# B137X.net
KiCad netlist of a schematic drawn in EAGLE
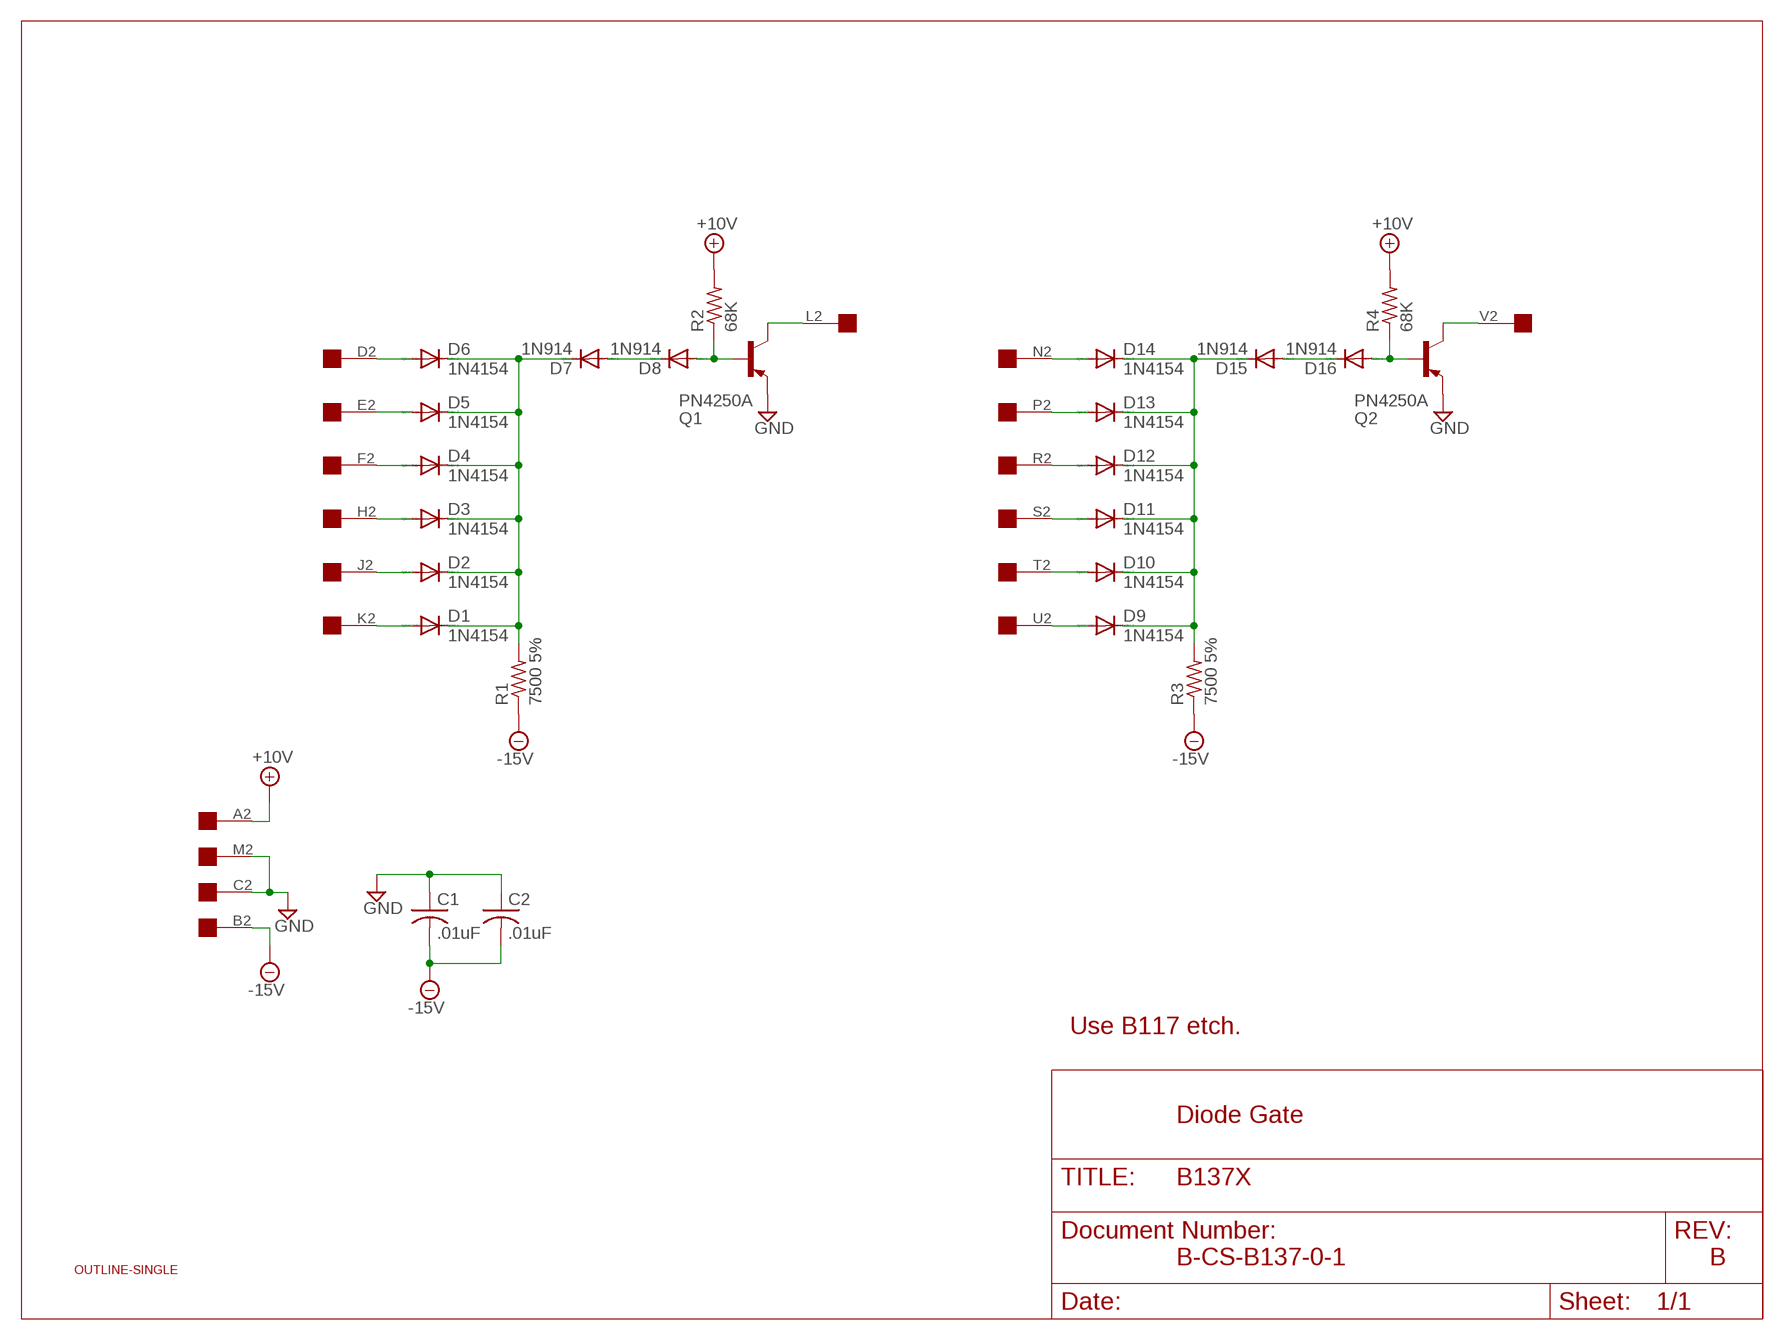
[diagram p0: schematic, sheet 1]

(export (version "E")
  (design (tool "Eeschema 10.0.6"))
  (components
    (comp (ref "C1")
      (value ".01uF")
      (footprint "eagle-import:C050-025X075")
      (libsource (lib "eagle-import") (part "C-US050-025X075"))
    )
    (comp (ref "C2")
      (value ".01uF")
      (footprint "eagle-import:C050-025X075")
      (libsource (lib "eagle-import") (part "C-US050-025X075"))
    )
    (comp (ref "D1")
      (value "1N4154")
      (footprint "eagle-import:DO35-10")
      (libsource (lib "eagle-import") (part "DIODE-DO35-10"))
    )
    (comp (ref "D2")
      (value "1N4154")
      (footprint "eagle-import:DO35-10")
      (libsource (lib "eagle-import") (part "DIODE-DO35-10"))
    )
    (comp (ref "D3")
      (value "1N4154")
      (footprint "eagle-import:DO35-10")
      (libsource (lib "eagle-import") (part "DIODE-DO35-10"))
    )
    (comp (ref "D4")
      (value "1N4154")
      (footprint "eagle-import:DO35-10")
      (libsource (lib "eagle-import") (part "DIODE-DO35-10"))
    )
    (comp (ref "D5")
      (value "1N4154")
      (footprint "eagle-import:DO35-10")
      (libsource (lib "eagle-import") (part "DIODE-DO35-10"))
    )
    (comp (ref "D6")
      (value "1N4154")
      (footprint "eagle-import:DO35-10")
      (libsource (lib "eagle-import") (part "DIODE-DO35-10"))
    )
    (comp (ref "D7")
      (value "1N914")
      (footprint "eagle-import:DO35-10")
      (libsource (lib "eagle-import") (part "DIODE-DO35-10"))
    )
    (comp (ref "D8")
      (value "1N914")
      (footprint "eagle-import:DO35-10")
      (libsource (lib "eagle-import") (part "DIODE-DO35-10"))
    )
    (comp (ref "D9")
      (value "1N4154")
      (footprint "eagle-import:DO35-10")
      (libsource (lib "eagle-import") (part "DIODE-DO35-10"))
    )
    (comp (ref "D10")
      (value "1N4154")
      (footprint "eagle-import:DO35-10")
      (libsource (lib "eagle-import") (part "DIODE-DO35-10"))
    )
    (comp (ref "D11")
      (value "1N4154")
      (footprint "eagle-import:DO35-10")
      (libsource (lib "eagle-import") (part "DIODE-DO35-10"))
    )
    (comp (ref "D12")
      (value "1N4154")
      (footprint "eagle-import:DO35-10")
      (libsource (lib "eagle-import") (part "DIODE-DO35-10"))
    )
    (comp (ref "D13")
      (value "1N4154")
      (footprint "eagle-import:DO35-10")
      (libsource (lib "eagle-import") (part "DIODE-DO35-10"))
    )
    (comp (ref "D14")
      (value "1N4154")
      (footprint "eagle-import:DO35-10")
      (libsource (lib "eagle-import") (part "DIODE-DO35-10"))
    )
    (comp (ref "D15")
      (value "1N914")
      (footprint "eagle-import:DO35-10")
      (libsource (lib "eagle-import") (part "DIODE-DO35-10"))
    )
    (comp (ref "D16")
      (value "1N914")
      (footprint "eagle-import:DO35-10")
      (libsource (lib "eagle-import") (part "DIODE-DO35-10"))
    )
    (comp (ref "Q1")
      (value "PN4250A")
      (footprint "eagle-import:TO5")
      (libsource (lib "eagle-import") (part "-PNP-TO5"))
    )
    (comp (ref "Q2")
      (value "PN4250A")
      (footprint "eagle-import:TO5")
      (libsource (lib "eagle-import") (part "-PNP-TO5"))
    )
    (comp (ref "R1")
      (value "7500 5%")
      (footprint "eagle-import:0207_10")
      (libsource (lib "eagle-import") (part "R-US_0207/10"))
    )
    (comp (ref "R2")
      (value "68K")
      (footprint "eagle-import:0207_10")
      (libsource (lib "eagle-import") (part "R-US_0207/10"))
    )
    (comp (ref "R3")
      (value "7500 5%")
      (footprint "eagle-import:0207_10")
      (libsource (lib "eagle-import") (part "R-US_0207/10"))
    )
    (comp (ref "R4")
      (value "68K")
      (footprint "eagle-import:0207_10")
      (libsource (lib "eagle-import") (part "R-US_0207/10"))
    )
    (comp (ref "U$1")
      (value "OUTLINE-SINGLE")
      (footprint "eagle-import:SINGLE")
      (libsource (lib "eagle-import") (part "OUTLINE-SINGLE"))
    )
    (comp (ref "U$2")
      (value "EDGE-1")
      (footprint "eagle-import:EDGE-CON1")
      (libsource (lib "eagle-import") (part "EDGE-1"))
    )
  )
  (nets
    (net (code "1") (name "+10V") (class "Default")
      (node (ref "R2") (pin "2") (pinfunction "2_2") (pintype "passive"))
      (node (ref "R4") (pin "2") (pinfunction "2_2") (pintype "passive"))
      (node (ref "U$2") (pin "A2") (pinfunction "1_A2") (pintype "bidirectional"))
    )
    (net (code "2") (name "-15V") (class "Default")
      (node (ref "C1") (pin "2") (pinfunction "2_2") (pintype "passive"))
      (node (ref "C2") (pin "2") (pinfunction "2_2") (pintype "passive"))
      (node (ref "R1") (pin "1") (pinfunction "1_1") (pintype "passive"))
      (node (ref "R3") (pin "1") (pinfunction "1_1") (pintype "passive"))
      (node (ref "U$2") (pin "B2") (pinfunction "1_B2") (pintype "bidirectional"))
    )
    (net (code "3") (name "GND") (class "Default")
      (node (ref "C1") (pin "1") (pinfunction "1_1") (pintype "passive"))
      (node (ref "C2") (pin "1") (pinfunction "1_1") (pintype "passive"))
      (node (ref "Q1") (pin "1") (pinfunction "E_1") (pintype "passive"))
      (node (ref "Q2") (pin "1") (pinfunction "E_1") (pintype "passive"))
      (node (ref "U$2") (pin "C2") (pinfunction "1_C2") (pintype "bidirectional"))
      (node (ref "U$2") (pin "M2") (pinfunction "1_M2") (pintype "bidirectional"))
    )
    (net (code "4") (name "Net-(D1-PadC)") (class "Default")
      (node (ref "D1") (pin "C") (pinfunction "C_C") (pintype "passive"))
      (node (ref "D2") (pin "C") (pinfunction "C_C") (pintype "passive"))
      (node (ref "D3") (pin "C") (pinfunction "C_C") (pintype "passive"))
      (node (ref "D4") (pin "C") (pinfunction "C_C") (pintype "passive"))
      (node (ref "D5") (pin "C") (pinfunction "C_C") (pintype "passive"))
      (node (ref "D6") (pin "C") (pinfunction "C_C") (pintype "passive"))
      (node (ref "D7") (pin "C") (pinfunction "C_C") (pintype "passive"))
      (node (ref "R1") (pin "2") (pinfunction "2_2") (pintype "passive"))
    )
    (net (code "5") (name "Net-(D7-PadA)") (class "Default")
      (node (ref "D7") (pin "A") (pinfunction "A_A") (pintype "passive"))
      (node (ref "D8") (pin "C") (pinfunction "C_C") (pintype "passive"))
    )
    (net (code "6") (name "Net-(D10-PadC)") (class "Default")
      (node (ref "D10") (pin "C") (pinfunction "C_C") (pintype "passive"))
      (node (ref "D11") (pin "C") (pinfunction "C_C") (pintype "passive"))
      (node (ref "D12") (pin "C") (pinfunction "C_C") (pintype "passive"))
      (node (ref "D13") (pin "C") (pinfunction "C_C") (pintype "passive"))
      (node (ref "D14") (pin "C") (pinfunction "C_C") (pintype "passive"))
      (node (ref "D15") (pin "C") (pinfunction "C_C") (pintype "passive"))
      (node (ref "D9") (pin "C") (pinfunction "C_C") (pintype "passive"))
      (node (ref "R3") (pin "2") (pinfunction "2_2") (pintype "passive"))
    )
    (net (code "7") (name "Net-(D15-PadA)") (class "Default")
      (node (ref "D15") (pin "A") (pinfunction "A_A") (pintype "passive"))
      (node (ref "D16") (pin "C") (pinfunction "C_C") (pintype "passive"))
    )
    (net (code "8") (name "Net-(Q1-B)") (class "Default")
      (node (ref "D8") (pin "A") (pinfunction "A_A") (pintype "passive"))
      (node (ref "Q1") (pin "2") (pinfunction "B_2") (pintype "passive"))
      (node (ref "R2") (pin "1") (pinfunction "1_1") (pintype "passive"))
    )
    (net (code "9") (name "Net-(Q1-C)") (class "Default")
      (node (ref "Q1") (pin "3") (pinfunction "C_3") (pintype "passive"))
      (node (ref "U$2") (pin "L2") (pinfunction "1_L2") (pintype "bidirectional"))
    )
    (net (code "10") (name "Net-(Q2-B)") (class "Default")
      (node (ref "D16") (pin "A") (pinfunction "A_A") (pintype "passive"))
      (node (ref "Q2") (pin "2") (pinfunction "B_2") (pintype "passive"))
      (node (ref "R4") (pin "1") (pinfunction "1_1") (pintype "passive"))
    )
    (net (code "11") (name "Net-(Q2-C)") (class "Default")
      (node (ref "Q2") (pin "3") (pinfunction "C_3") (pintype "passive"))
      (node (ref "U$2") (pin "V2") (pinfunction "1_V2") (pintype "bidirectional"))
    )
    (net (code "12") (name "Net-(U$2D-1)") (class "Default")
      (node (ref "D6") (pin "A") (pinfunction "A_A") (pintype "passive"))
      (node (ref "U$2") (pin "D2") (pinfunction "1_D2") (pintype "bidirectional"))
    )
    (net (code "13") (name "Net-(U$2E-1)") (class "Default")
      (node (ref "D5") (pin "A") (pinfunction "A_A") (pintype "passive"))
      (node (ref "U$2") (pin "E2") (pinfunction "1_E2") (pintype "bidirectional"))
    )
    (net (code "14") (name "Net-(U$2F-1)") (class "Default")
      (node (ref "D4") (pin "A") (pinfunction "A_A") (pintype "passive"))
      (node (ref "U$2") (pin "F2") (pinfunction "1_F2") (pintype "bidirectional"))
    )
    (net (code "15") (name "Net-(U$2G-1)") (class "Default")
      (node (ref "D3") (pin "A") (pinfunction "A_A") (pintype "passive"))
      (node (ref "U$2") (pin "H2") (pinfunction "1_H2") (pintype "bidirectional"))
    )
    (net (code "16") (name "Net-(U$2H-1)") (class "Default")
      (node (ref "D2") (pin "A") (pinfunction "A_A") (pintype "passive"))
      (node (ref "U$2") (pin "J2") (pinfunction "1_J2") (pintype "bidirectional"))
    )
    (net (code "17") (name "Net-(U$2I-1)") (class "Default")
      (node (ref "D1") (pin "A") (pinfunction "A_A") (pintype "passive"))
      (node (ref "U$2") (pin "K2") (pinfunction "1_K2") (pintype "bidirectional"))
    )
    (net (code "18") (name "Net-(U$2L-1)") (class "Default")
      (node (ref "D14") (pin "A") (pinfunction "A_A") (pintype "passive"))
      (node (ref "U$2") (pin "N2") (pinfunction "1_N2") (pintype "bidirectional"))
    )
    (net (code "19") (name "Net-(U$2M-1)") (class "Default")
      (node (ref "D13") (pin "A") (pinfunction "A_A") (pintype "passive"))
      (node (ref "U$2") (pin "P2") (pinfunction "1_P2") (pintype "bidirectional"))
    )
    (net (code "20") (name "Net-(U$2N-1)") (class "Default")
      (node (ref "D12") (pin "A") (pinfunction "A_A") (pintype "passive"))
      (node (ref "U$2") (pin "R2") (pinfunction "1_R2") (pintype "bidirectional"))
    )
    (net (code "21") (name "Net-(U$2O-1)") (class "Default")
      (node (ref "D11") (pin "A") (pinfunction "A_A") (pintype "passive"))
      (node (ref "U$2") (pin "S2") (pinfunction "1_S2") (pintype "bidirectional"))
    )
    (net (code "22") (name "Net-(U$2P-1)") (class "Default")
      (node (ref "D10") (pin "A") (pinfunction "A_A") (pintype "passive"))
      (node (ref "U$2") (pin "T2") (pinfunction "1_T2") (pintype "bidirectional"))
    )
    (net (code "23") (name "Net-(U$2Q-1)") (class "Default")
      (node (ref "D9") (pin "A") (pinfunction "A_A") (pintype "passive"))
      (node (ref "U$2") (pin "U2") (pinfunction "1_U2") (pintype "bidirectional"))
    )
  )
)
